# Communication.net
KiCad netlist of a schematic drawn in Altium Designer
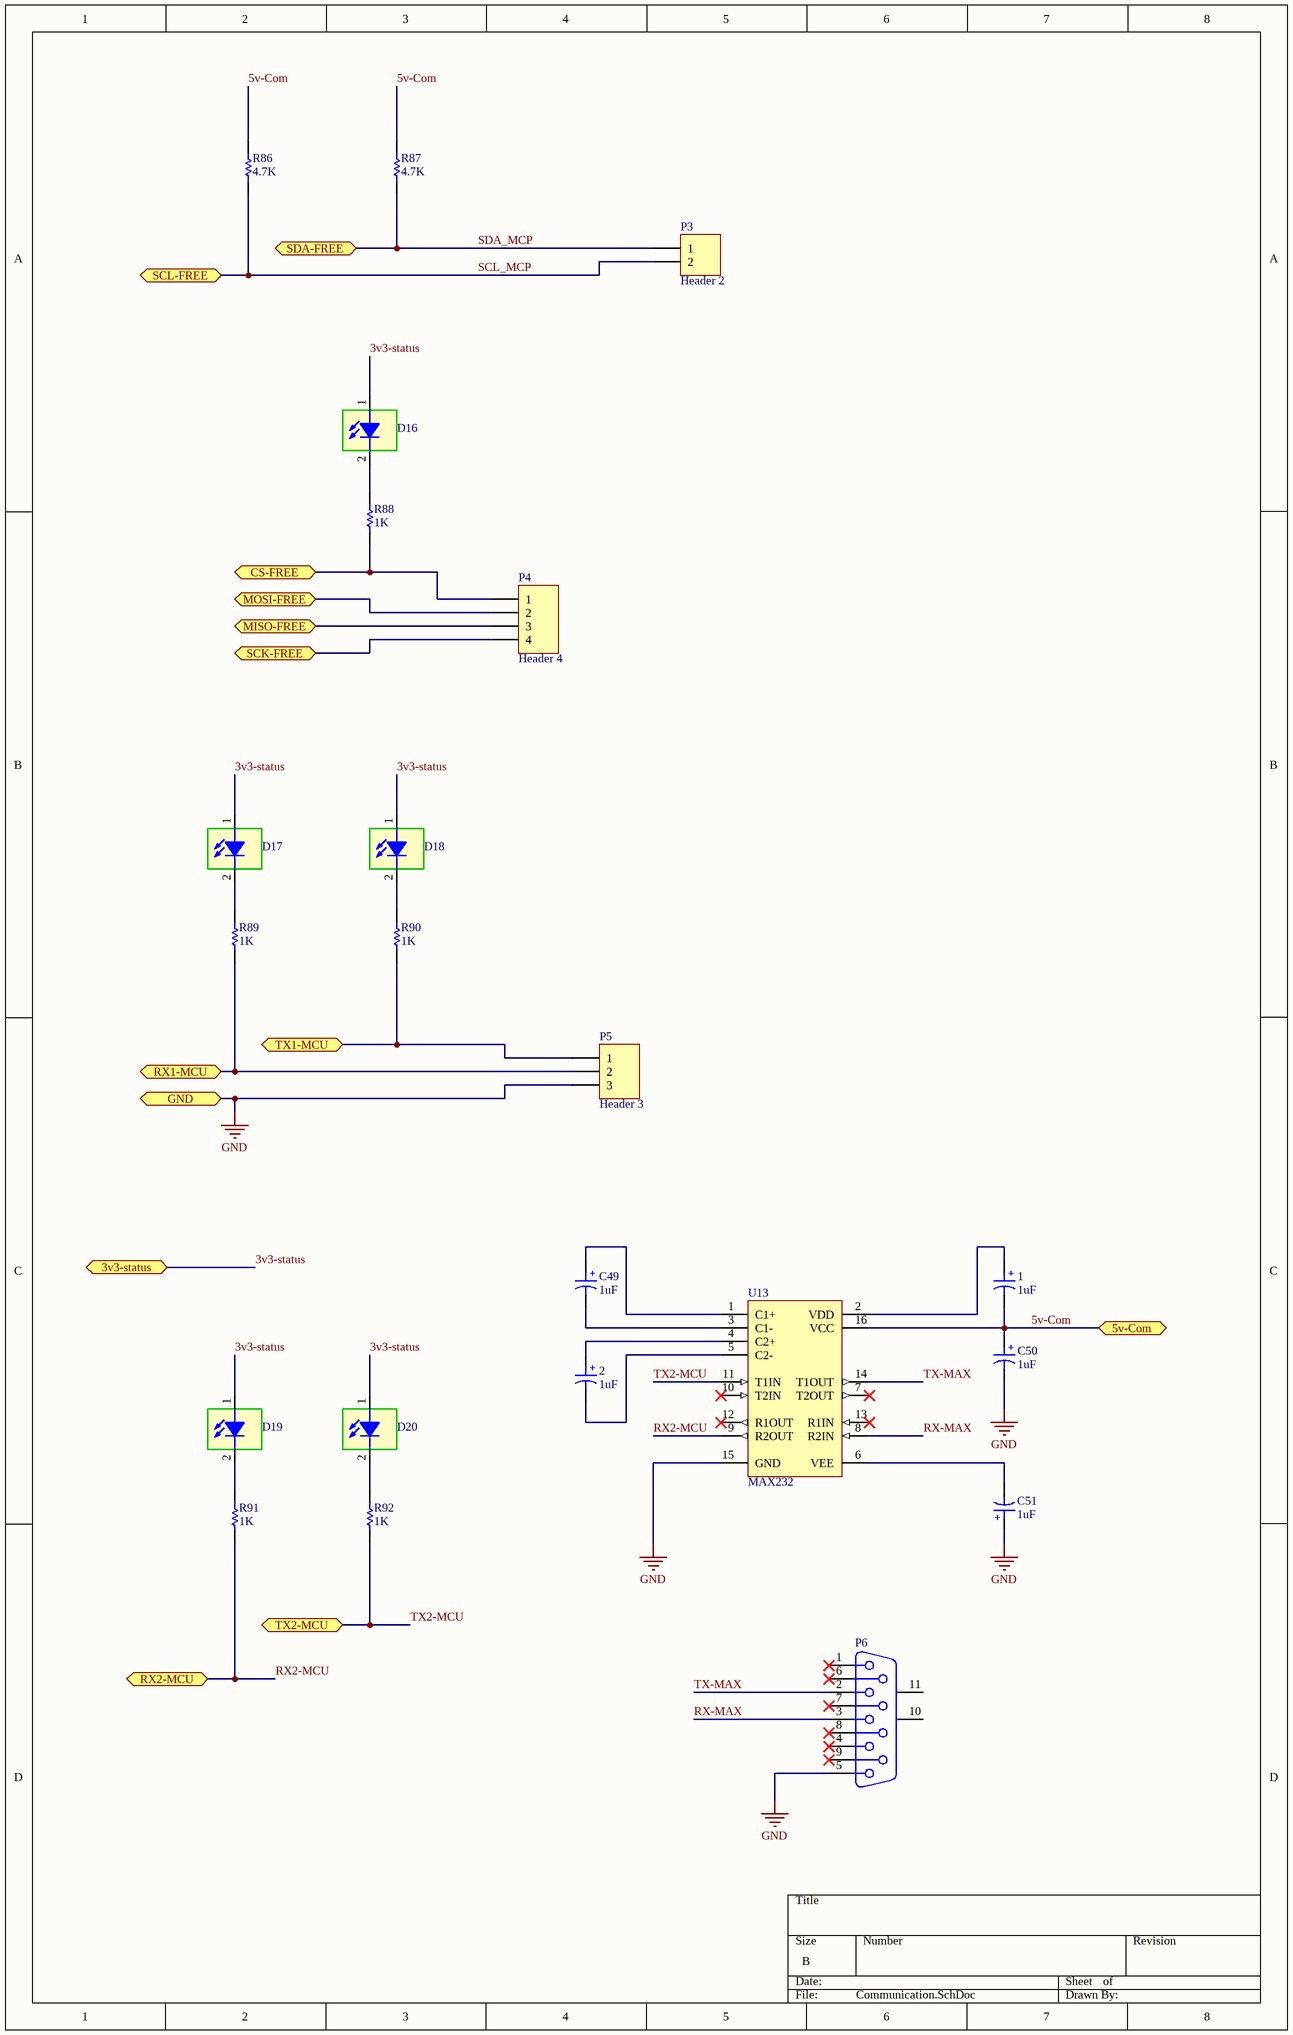
[diagram p0: Communication.SchDoc]

(export (version "E")
  (design (tool "Eeschema 10.0.6"))
  (components
    (comp (ref "1")
      (value "1uF")
      (footprint "Cap1206_(3216X18L)Size A")
      (description "Cap electrolitic radial")
      (fields (field (name "DESIGNER") "Abbas Basereh"))
      (libsource (lib "Altium") (part "Cap ELECTROLITIC TOTAL SIZE"))
    )
    (comp (ref "2")
      (value "1uF")
      (footprint "Cap1206_(3216X18L)Size A")
      (description "Cap electrolitic radial")
      (fields (field (name "DESIGNER") "Abbas Basereh"))
      (libsource (lib "Altium") (part "Cap ELECTROLITIC TOTAL SIZE"))
    )
    (comp (ref "C49")
      (value "1uF")
      (footprint "Cap1206_(3216X18L)Size A")
      (description "Cap electrolitic radial")
      (fields (field (name "DESIGNER") "Abbas Basereh"))
      (libsource (lib "Altium") (part "Cap ELECTROLITIC TOTAL SIZE"))
    )
    (comp (ref "C50")
      (value "1uF")
      (footprint "Cap1206_(3216X18L)Size A")
      (description "Cap electrolitic radial")
      (fields (field (name "DESIGNER") "Abbas Basereh"))
      (libsource (lib "Altium") (part "Cap ELECTROLITIC TOTAL SIZE"))
    )
    (comp (ref "C51")
      (value "1uF")
      (footprint "Cap1206_(3216X18L)Size A")
      (description "Cap electrolitic radial")
      (fields (field (name "DESIGNER") "Abbas Basereh"))
      (libsource (lib "Altium") (part "Cap ELECTROLITIC TOTAL SIZE"))
    )
    (comp (ref "D16")
      (value "SMD 1206 LED")
      (footprint "LED 1206")
      (libsource (lib "Altium") (part "LED SMD 1206"))
    )
    (comp (ref "D17")
      (value "SMD 1206 LED")
      (footprint "LED 1206")
      (libsource (lib "Altium") (part "LED SMD 1206"))
    )
    (comp (ref "D18")
      (value "SMD 1206 LED")
      (footprint "LED 1206")
      (libsource (lib "Altium") (part "LED SMD 1206"))
    )
    (comp (ref "D19")
      (value "SMD 1206 LED")
      (footprint "LED 1206")
      (libsource (lib "Altium") (part "LED SMD 1206"))
    )
    (comp (ref "D20")
      (value "SMD 1206 LED")
      (footprint "LED 1206")
      (libsource (lib "Altium") (part "LED SMD 1206"))
    )
    (comp (ref "P3")
      (value "Header 2")
      (footprint "HDR1X2")
      (description "Header, 2-Pin")
      (fields (field (name "PUBLISHER") "Altium Limited"))
      (libsource (lib "Altium") (part "Header 2"))
    )
    (comp (ref "P4")
      (value "Header 4")
      (footprint "HDR1X4")
      (description "Header, 4-Pin")
      (fields (field (name "PUBLISHER") "Altium Limited"))
      (libsource (lib "Altium") (part "Header 4"))
    )
    (comp (ref "P5")
      (value "Header 3")
      (footprint "HDR1X3")
      (description "Header, 3-Pin")
      (fields (field (name "PUBLISHER") "Altium Limited"))
      (libsource (lib "Altium") (part "Header 3"))
    )
    (comp (ref "P6")
      (value "DB9 Connector")
      (footprint "DB9 Female")
      (description "Receptacle Assembly, 9 Position, Right Angle")
      (fields (field (name "PUBLISHER") "Altium Limited"))
      (libsource (lib "Altium") (part "DB9 Connector"))
    )
    (comp (ref "R86")
      (value "4.7K")
      (footprint "RESC3413X04N")
      (description "RES 0805")
      (fields (field (name "DESIGNER") "Abbas Basereh"))
      (libsource (lib "Altium") (part "RES 0805 0.125W"))
    )
    (comp (ref "R87")
      (value "4.7K")
      (footprint "RESC3413X04N")
      (description "RES 0805")
      (fields (field (name "DESIGNER") "Abbas Basereh"))
      (libsource (lib "Altium") (part "RES 0805 0.125W"))
    )
    (comp (ref "R88")
      (value "1K")
      (footprint "RESC3413X04N")
      (description "RES 0805")
      (fields (field (name "DESIGNER") "Abbas Basereh"))
      (libsource (lib "Altium") (part "RES 0805 0.125W"))
    )
    (comp (ref "R89")
      (value "1K")
      (footprint "RESC3413X04N")
      (description "RES 0805")
      (fields (field (name "DESIGNER") "Abbas Basereh"))
      (libsource (lib "Altium") (part "RES 0805 0.125W"))
    )
    (comp (ref "R90")
      (value "1K")
      (footprint "RESC3413X04N")
      (description "RES 0805")
      (fields (field (name "DESIGNER") "Abbas Basereh"))
      (libsource (lib "Altium") (part "RES 0805 0.125W"))
    )
    (comp (ref "R91")
      (value "1K")
      (footprint "RESC3413X04N")
      (description "RES 0805")
      (fields (field (name "DESIGNER") "Abbas Basereh"))
      (libsource (lib "Altium") (part "RES 0805 0.125W"))
    )
    (comp (ref "R92")
      (value "1K")
      (footprint "RESC3413X04N")
      (description "RES 0805")
      (fields (field (name "DESIGNER") "Abbas Basereh"))
      (libsource (lib "Altium") (part "RES 0805 0.125W"))
    )
    (comp (ref "U13")
      (value "MAX232")
      (footprint "SOIC-16")
      (description "+5V Powered RS-232 Driver/Receiver")
      (fields (field (name "PUBLISHER") "Altium Limited"))
      (libsource (lib "My_LIB") (part "MAX232"))
    )
  )
  (nets
    (net (code "1") (name "/3v3-status") (class "Default")
      (node (ref "D16") (pin "1") (pinfunction "1_1") (pintype "passive"))
      (node (ref "D17") (pin "1") (pinfunction "1_1") (pintype "passive"))
      (node (ref "D18") (pin "1") (pinfunction "1_1") (pintype "passive"))
      (node (ref "D19") (pin "1") (pinfunction "1_1") (pintype "passive"))
      (node (ref "D20") (pin "1") (pinfunction "1_1") (pintype "passive"))
    )
    (net (code "2") (name "/5v-Com") (class "Default")
      (node (ref "1") (pin "2") (pinfunction "2_2") (pintype "passive"))
      (node (ref "C50") (pin "1") (pinfunction "1_1") (pintype "passive"))
      (node (ref "R86") (pin "2") (pinfunction "2_2") (pintype "passive"))
      (node (ref "R87") (pin "2") (pinfunction "2_2") (pintype "passive"))
      (node (ref "U13") (pin "16") (pinfunction "VCC_16") (pintype "power_in"))
    )
    (net (code "3") (name "/CS-FREE") (class "Default")
      (node (ref "P4") (pin "1") (pinfunction "1_1") (pintype "passive"))
      (node (ref "R88") (pin "1") (pinfunction "1_1") (pintype "passive"))
    )
    (net (code "4") (name "/MISO-FREE") (class "Default")
      (node (ref "P4") (pin "3") (pinfunction "3_3") (pintype "passive"))
    )
    (net (code "5") (name "/MOSI-FREE") (class "Default")
      (node (ref "P4") (pin "2") (pinfunction "2_2") (pintype "passive"))
    )
    (net (code "6") (name "/RX-MAX") (class "Default")
      (node (ref "P6") (pin "3") (pinfunction "3_3") (pintype "passive"))
      (node (ref "U13") (pin "8") (pinfunction "R2IN_8") (pintype "input"))
    )
    (net (code "7") (name "/RX1-MCU") (class "Default")
      (node (ref "P5") (pin "2") (pinfunction "2_2") (pintype "passive"))
      (node (ref "R89") (pin "1") (pinfunction "1_1") (pintype "passive"))
    )
    (net (code "8") (name "/RX2-MCU") (class "Default")
      (node (ref "R91") (pin "1") (pinfunction "1_1") (pintype "passive"))
      (node (ref "U13") (pin "9") (pinfunction "R2OUT_9") (pintype "output"))
    )
    (net (code "9") (name "/SCK-FREE") (class "Default")
      (node (ref "P4") (pin "4") (pinfunction "4_4") (pintype "passive"))
    )
    (net (code "10") (name "/SCL_MCP") (class "Default")
      (node (ref "P3") (pin "2") (pinfunction "2_2") (pintype "passive"))
      (node (ref "R86") (pin "1") (pinfunction "1_1") (pintype "passive"))
    )
    (net (code "11") (name "/SDA_MCP") (class "Default")
      (node (ref "P3") (pin "1") (pinfunction "1_1") (pintype "passive"))
      (node (ref "R87") (pin "1") (pinfunction "1_1") (pintype "passive"))
    )
    (net (code "12") (name "/TX-MAX") (class "Default")
      (node (ref "P6") (pin "2") (pinfunction "2_2") (pintype "passive"))
      (node (ref "U13") (pin "14") (pinfunction "T1OUT_14") (pintype "output"))
    )
    (net (code "13") (name "/TX1-MCU") (class "Default")
      (node (ref "P5") (pin "1") (pinfunction "1_1") (pintype "passive"))
      (node (ref "R90") (pin "1") (pinfunction "1_1") (pintype "passive"))
    )
    (net (code "14") (name "/TX2-MCU") (class "Default")
      (node (ref "R92") (pin "1") (pinfunction "1_1") (pintype "passive"))
      (node (ref "U13") (pin "11") (pinfunction "T1IN_11") (pintype "input"))
    )
    (net (code "15") (name "GND") (class "Default")
      (node (ref "C50") (pin "2") (pinfunction "2_2") (pintype "passive"))
      (node (ref "C51") (pin "1") (pinfunction "1_1") (pintype "passive"))
      (node (ref "P5") (pin "3") (pinfunction "3_3") (pintype "passive"))
      (node (ref "P6") (pin "5") (pinfunction "5_5") (pintype "passive"))
      (node (ref "U13") (pin "15") (pinfunction "GND_15") (pintype "power_in"))
    )
    (net (code "16") (name "Net-(D16-Pad2)") (class "Default")
      (node (ref "D16") (pin "2") (pinfunction "2_2") (pintype "passive"))
      (node (ref "R88") (pin "2") (pinfunction "2_2") (pintype "passive"))
    )
    (net (code "17") (name "Net-(D17-Pad2)") (class "Default")
      (node (ref "D17") (pin "2") (pinfunction "2_2") (pintype "passive"))
      (node (ref "R89") (pin "2") (pinfunction "2_2") (pintype "passive"))
    )
    (net (code "18") (name "Net-(D18-Pad2)") (class "Default")
      (node (ref "D18") (pin "2") (pinfunction "2_2") (pintype "passive"))
      (node (ref "R90") (pin "2") (pinfunction "2_2") (pintype "passive"))
    )
    (net (code "19") (name "Net-(D19-Pad2)") (class "Default")
      (node (ref "D19") (pin "2") (pinfunction "2_2") (pintype "passive"))
      (node (ref "R91") (pin "2") (pinfunction "2_2") (pintype "passive"))
    )
    (net (code "20") (name "Net-(D20-Pad2)") (class "Default")
      (node (ref "D20") (pin "2") (pinfunction "2_2") (pintype "passive"))
      (node (ref "R92") (pin "2") (pinfunction "2_2") (pintype "passive"))
    )
    (net (code "21") (name "Net-(U13-C1+)") (class "Default")
      (node (ref "C49") (pin "1") (pinfunction "1_1") (pintype "passive"))
      (node (ref "U13") (pin "1") (pinfunction "C1+_1") (pintype "passive"))
    )
    (net (code "22") (name "Net-(U13-C1-)") (class "Default")
      (node (ref "C49") (pin "2") (pinfunction "2_2") (pintype "passive"))
      (node (ref "U13") (pin "3") (pinfunction "C1-_3") (pintype "passive"))
    )
    (net (code "23") (name "Net-(U13-C2+)") (class "Default")
      (node (ref "2") (pin "1") (pinfunction "1_1") (pintype "passive"))
      (node (ref "U13") (pin "4") (pinfunction "C2+_4") (pintype "passive"))
    )
    (net (code "24") (name "Net-(U13-C2-)") (class "Default")
      (node (ref "2") (pin "2") (pinfunction "2_2") (pintype "passive"))
      (node (ref "U13") (pin "5") (pinfunction "C2-_5") (pintype "passive"))
    )
    (net (code "25") (name "Net-(U13-VDD)") (class "Default")
      (node (ref "1") (pin "1") (pinfunction "1_1") (pintype "passive"))
      (node (ref "U13") (pin "2") (pinfunction "VDD_2") (pintype "power_in"))
    )
    (net (code "26") (name "Net-(U13-VEE)") (class "Default")
      (node (ref "C51") (pin "2") (pinfunction "2_2") (pintype "passive"))
      (node (ref "U13") (pin "6") (pinfunction "VEE_6") (pintype "power_in"))
    )
    (net (code "27") (name "unconnected-(P6-MH1-Pad10)") (class "Default")
      (node (ref "P6") (pin "10") (pinfunction "MH1_10") (pintype "passive"))
    )
    (net (code "28") (name "unconnected-(P6-MH2-Pad11)") (class "Default")
      (node (ref "P6") (pin "11") (pinfunction "MH2_11") (pintype "passive"))
    )
    (net (code "29") (name "unconnected-(P6-Pad1)") (class "Default")
      (node (ref "P6") (pin "1") (pinfunction "1_1") (pintype "passive+no_connect"))
    )
    (net (code "30") (name "unconnected-(P6-Pad4)") (class "Default")
      (node (ref "P6") (pin "4") (pinfunction "4_4") (pintype "passive+no_connect"))
    )
    (net (code "31") (name "unconnected-(P6-Pad6)") (class "Default")
      (node (ref "P6") (pin "6") (pinfunction "6_6") (pintype "passive+no_connect"))
    )
    (net (code "32") (name "unconnected-(P6-Pad7)") (class "Default")
      (node (ref "P6") (pin "7") (pinfunction "7_7") (pintype "passive+no_connect"))
    )
    (net (code "33") (name "unconnected-(P6-Pad8)") (class "Default")
      (node (ref "P6") (pin "8") (pinfunction "8_8") (pintype "passive+no_connect"))
    )
    (net (code "34") (name "unconnected-(P6-Pad9)") (class "Default")
      (node (ref "P6") (pin "9") (pinfunction "9_9") (pintype "passive+no_connect"))
    )
    (net (code "35") (name "unconnected-(U13-R1IN-Pad13)") (class "Default")
      (node (ref "U13") (pin "13") (pinfunction "R1IN_13") (pintype "input+no_connect"))
    )
    (net (code "36") (name "unconnected-(U13-R1OUT-Pad12)") (class "Default")
      (node (ref "U13") (pin "12") (pinfunction "R1OUT_12") (pintype "output+no_connect"))
    )
    (net (code "37") (name "unconnected-(U13-T2IN-Pad10)") (class "Default")
      (node (ref "U13") (pin "10") (pinfunction "T2IN_10") (pintype "input+no_connect"))
    )
    (net (code "38") (name "unconnected-(U13-T2OUT-Pad7)") (class "Default")
      (node (ref "U13") (pin "7") (pinfunction "T2OUT_7") (pintype "output+no_connect"))
    )
  )
)
